# Esquema_Dispositivo.net
KiCad netlist of a schematic drawn in Altium Designer
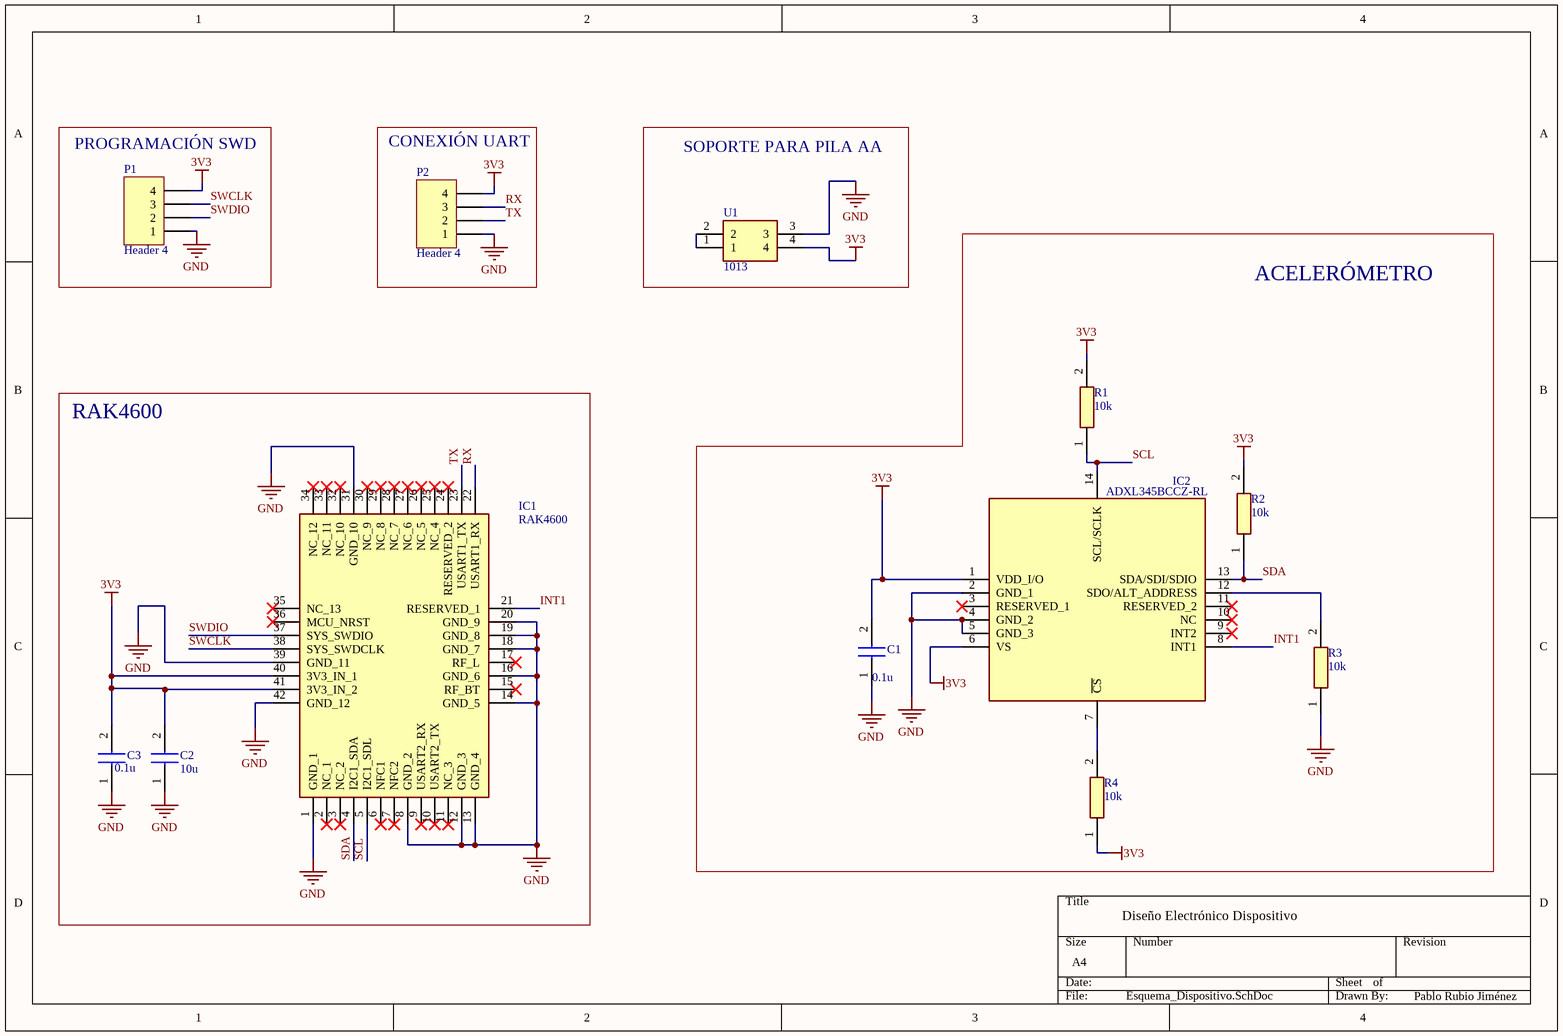
[diagram p0: Esquema_Dispositivo.SchDoc]

(export (version "E")
  (design (tool "Eeschema 10.0.6"))
  (components
    (comp (ref "C1")
      (value "0.1u")
      (footprint "SamacSys:CAPC2012X98N")
      (description "Capacitor")
      (fields
        (field (name "MANUFACTURER_PART_NUMBER") "C0805X104M5RACTU")
        (field (name "MOUSER PART NUMBER") "80-C0805X104M5RACTU")
      )
      (libsource (lib "*") (part "C0805X104M5RACTU"))
    )
    (comp (ref "C2")
      (value "10u")
      (footprint "SamacSys:CAPC1608X90N")
      (description "Capacitor")
      (fields
        (field (name "MANUFACTURER_PART_NUMBER") "0603ZD106KAT2A")
        (field (name "MOUSER PART NUMBER") "581-0603ZD106KAT2A")
      )
      (libsource (lib "*") (part "0603ZD106KAT2A"))
    )
    (comp (ref "C3")
      (value "0.1u")
      (footprint "SamacSys:CAPC2012X98N")
      (description "Capacitor")
      (fields
        (field (name "MANUFACTURER_PART_NUMBER") "C0805X104M5RACTU")
        (field (name "MOUSER PART NUMBER") "80-C0805X104M5RACTU")
      )
      (libsource (lib "*") (part "C0805X104M5RACTU"))
    )
    (comp (ref "IC1")
      (value "RAK4600")
      (footprint "SamacSys:RAK4600")
      (description "Integrated Circuit")
      (libsource (lib "SamacSys") (part "RAK4600"))
    )
    (comp (ref "IC2")
      (value "ADXL345BCCZ-RL")
      (footprint "SamacSys:ADXL345BCCZRL")
      (description "Integrated Circuit")
      (fields (field (name "MOUSER PART NUMBER") "584-ADXL345BCCZ-R"))
      (libsource (lib "*") (part "ADXL345BCCZ-RL"))
    )
    (comp (ref "P1")
      (value "Header 4")
      (footprint "HDR1X4")
      (description "Header, 4-Pin")
      (fields (field (name "PUBLISHER") "Altium Limited"))
      (libsource (lib "Miscellaneous Connectors") (part "Header 4"))
    )
    (comp (ref "P2")
      (value "Header 4")
      (footprint "HDR1X4")
      (description "Header, 4-Pin")
      (fields (field (name "PUBLISHER") "Altium Limited"))
      (libsource (lib "Miscellaneous Connectors") (part "Header 4"))
    )
    (comp (ref "R1")
      (value "10k")
      (footprint "SamacSys:RESC1005X35N")
      (description "Resistor")
      (fields
        (field (name "MANUFACTURER_PART_NUMBER") "CPF0402B10KE")
        (field (name "MOUSER PART NUMBER") "279-CPF0402B10KE")
      )
      (libsource (lib "*") (part "CPF0402B10KE"))
    )
    (comp (ref "R2")
      (value "10k")
      (footprint "SamacSys:RESC1005X35N")
      (description "Resistor")
      (fields
        (field (name "MANUFACTURER_PART_NUMBER") "CPF0402B10KE")
        (field (name "MOUSER PART NUMBER") "279-CPF0402B10KE")
      )
      (libsource (lib "*") (part "CPF0402B10KE"))
    )
    (comp (ref "R3")
      (value "10k")
      (footprint "SamacSys:RESC1005X35N")
      (description "Resistor")
      (fields
        (field (name "MANUFACTURER_PART_NUMBER") "CPF0402B10KE")
        (field (name "MOUSER PART NUMBER") "279-CPF0402B10KE")
      )
      (libsource (lib "*") (part "CPF0402B10KE"))
    )
    (comp (ref "R4")
      (value "10k")
      (footprint "SamacSys:RESC1005X35N")
      (description "Resistor")
      (fields
        (field (name "MANUFACTURER_PART_NUMBER") "CPF0402B10KE")
        (field (name "MOUSER PART NUMBER") "279-CPF0402B10KE")
      )
      (libsource (lib "*") (part "CPF0402B10KE"))
    )
    (comp (ref "U1")
      (value "1013")
      (footprint "SamacSys:1013")
      (description "Undefined or Miscellaneous")
      (fields (field (name "MOUSER PART NUMBER") "534-1013"))
      (libsource (lib "*") (part "1013"))
    )
  )
  (nets
    (net (code "1") (name "/INT1") (class "Default")
      (node (ref "IC1") (pin "21") (pinfunction "RESERVED_1_21") (pintype "passive"))
      (node (ref "IC2") (pin "8") (pinfunction "INT1_8") (pintype "passive"))
    )
    (net (code "2") (name "/RX") (class "Default")
      (node (ref "IC1") (pin "22") (pinfunction "USART1_RX_22") (pintype "passive"))
      (node (ref "P2") (pin "3") (pinfunction "3_3") (pintype "passive"))
    )
    (net (code "3") (name "/SCL") (class "Default")
      (node (ref "IC1") (pin "5") (pinfunction "I2C1_SDL_5") (pintype "passive"))
      (node (ref "IC2") (pin "14") (pinfunction "SCL/SCLK_14") (pintype "passive"))
      (node (ref "R1") (pin "1") (pinfunction "1_1") (pintype "passive"))
    )
    (net (code "4") (name "/SDA") (class "Default")
      (node (ref "IC1") (pin "4") (pinfunction "I2C1_SDA_4") (pintype "passive"))
      (node (ref "IC2") (pin "13") (pinfunction "SDA/SDI/SDIO_13") (pintype "passive"))
      (node (ref "R2") (pin "1") (pinfunction "1_1") (pintype "passive"))
    )
    (net (code "5") (name "/SWCLK") (class "Default")
      (node (ref "IC1") (pin "38") (pinfunction "SYS_SWDCLK_38") (pintype "passive"))
      (node (ref "P1") (pin "3") (pinfunction "3_3") (pintype "passive"))
    )
    (net (code "6") (name "/SWDIO") (class "Default")
      (node (ref "IC1") (pin "37") (pinfunction "SYS_SWDIO_37") (pintype "passive"))
      (node (ref "P1") (pin "2") (pinfunction "2_2") (pintype "passive"))
    )
    (net (code "7") (name "/TX") (class "Default")
      (node (ref "IC1") (pin "23") (pinfunction "USART1_TX_23") (pintype "passive"))
      (node (ref "P2") (pin "2") (pinfunction "2_2") (pintype "passive"))
    )
    (net (code "8") (name "3V3") (class "Default")
      (node (ref "C1") (pin "2") (pinfunction "2_2") (pintype "passive"))
      (node (ref "C2") (pin "2") (pinfunction "2_2") (pintype "passive"))
      (node (ref "C3") (pin "2") (pinfunction "2_2") (pintype "passive"))
      (node (ref "IC1") (pin "40") (pinfunction "3V3_IN_1_40") (pintype "passive"))
      (node (ref "IC1") (pin "41") (pinfunction "3V3_IN_2_41") (pintype "passive"))
      (node (ref "IC2") (pin "1") (pinfunction "VDD_I/O_1") (pintype "passive"))
      (node (ref "IC2") (pin "6") (pinfunction "VS_6") (pintype "passive"))
      (node (ref "P1") (pin "4") (pinfunction "4_4") (pintype "passive"))
      (node (ref "P2") (pin "4") (pinfunction "4_4") (pintype "passive"))
      (node (ref "R1") (pin "2") (pinfunction "2_2") (pintype "passive"))
      (node (ref "R2") (pin "2") (pinfunction "2_2") (pintype "passive"))
      (node (ref "R4") (pin "1") (pinfunction "1_1") (pintype "passive"))
      (node (ref "U1") (pin "4") (pinfunction "4_4") (pintype "passive"))
    )
    (net (code "9") (name "GND") (class "Default")
      (node (ref "C1") (pin "1") (pinfunction "1_1") (pintype "passive"))
      (node (ref "C2") (pin "1") (pinfunction "1_1") (pintype "passive"))
      (node (ref "C3") (pin "1") (pinfunction "1_1") (pintype "passive"))
      (node (ref "IC1") (pin "1") (pinfunction "GND_1_1") (pintype "passive"))
      (node (ref "IC1") (pin "12") (pinfunction "GND_3_12") (pintype "passive"))
      (node (ref "IC1") (pin "13") (pinfunction "GND_4_13") (pintype "passive"))
      (node (ref "IC1") (pin "14") (pinfunction "GND_5_14") (pintype "passive"))
      (node (ref "IC1") (pin "16") (pinfunction "GND_6_16") (pintype "passive"))
      (node (ref "IC1") (pin "18") (pinfunction "GND_7_18") (pintype "passive"))
      (node (ref "IC1") (pin "19") (pinfunction "GND_8_19") (pintype "passive"))
      (node (ref "IC1") (pin "20") (pinfunction "GND_9_20") (pintype "passive"))
      (node (ref "IC1") (pin "31") (pinfunction "GND_10_31") (pintype "passive"))
      (node (ref "IC1") (pin "39") (pinfunction "GND_11_39") (pintype "passive"))
      (node (ref "IC1") (pin "42") (pinfunction "GND_12_42") (pintype "passive"))
      (node (ref "IC1") (pin "8") (pinfunction "GND_2_8") (pintype "passive"))
      (node (ref "IC2") (pin "2") (pinfunction "GND_1_2") (pintype "passive"))
      (node (ref "IC2") (pin "4") (pinfunction "GND_2_4") (pintype "passive"))
      (node (ref "IC2") (pin "5") (pinfunction "GND_3_5") (pintype "passive"))
      (node (ref "P1") (pin "1") (pinfunction "1_1") (pintype "passive"))
      (node (ref "P2") (pin "1") (pinfunction "1_1") (pintype "passive"))
      (node (ref "R3") (pin "1") (pinfunction "1_1") (pintype "passive"))
      (node (ref "U1") (pin "3") (pinfunction "3_3") (pintype "passive"))
    )
    (net (code "10") (name "Net-(IC2-SDO{slash}ALT_ADDRESS)") (class "Default")
      (node (ref "IC2") (pin "12") (pinfunction "SDO/ALT_ADDRESS_12") (pintype "passive"))
      (node (ref "R3") (pin "2") (pinfunction "2_2") (pintype "passive"))
    )
    (net (code "11") (name "Net-(IC2-~{CS})") (class "Default")
      (node (ref "IC2") (pin "7") (pinfunction "~{CS}_7") (pintype "passive"))
      (node (ref "R4") (pin "2") (pinfunction "2_2") (pintype "passive"))
    )
    (net (code "12") (name "Net-(U1-Pad1)") (class "Default")
      (node (ref "U1") (pin "1") (pinfunction "1_1") (pintype "passive"))
      (node (ref "U1") (pin "2") (pinfunction "2_2") (pintype "passive"))
    )
    (net (code "13") (name "unconnected-(IC1-MCU_NRST-Pad36)") (class "Default")
      (node (ref "IC1") (pin "36") (pinfunction "MCU_NRST_36") (pintype "passive+no_connect"))
    )
    (net (code "14") (name "unconnected-(IC1-NC_1-Pad2)") (class "Default")
      (node (ref "IC1") (pin "2") (pinfunction "NC_1_2") (pintype "passive+no_connect"))
    )
    (net (code "15") (name "unconnected-(IC1-NC_2-Pad3)") (class "Default")
      (node (ref "IC1") (pin "3") (pinfunction "NC_2_3") (pintype "passive+no_connect"))
    )
    (net (code "16") (name "unconnected-(IC1-NC_3-Pad11)") (class "Default")
      (node (ref "IC1") (pin "11") (pinfunction "NC_3_11") (pintype "passive+no_connect"))
    )
    (net (code "17") (name "unconnected-(IC1-NC_4-Pad25)") (class "Default")
      (node (ref "IC1") (pin "25") (pinfunction "NC_4_25") (pintype "passive+no_connect"))
    )
    (net (code "18") (name "unconnected-(IC1-NC_5-Pad26)") (class "Default")
      (node (ref "IC1") (pin "26") (pinfunction "NC_5_26") (pintype "passive+no_connect"))
    )
    (net (code "19") (name "unconnected-(IC1-NC_6-Pad27)") (class "Default")
      (node (ref "IC1") (pin "27") (pinfunction "NC_6_27") (pintype "passive+no_connect"))
    )
    (net (code "20") (name "unconnected-(IC1-NC_7-Pad28)") (class "Default")
      (node (ref "IC1") (pin "28") (pinfunction "NC_7_28") (pintype "passive+no_connect"))
    )
    (net (code "21") (name "unconnected-(IC1-NC_8-Pad29)") (class "Default")
      (node (ref "IC1") (pin "29") (pinfunction "NC_8_29") (pintype "passive+no_connect"))
    )
    (net (code "22") (name "unconnected-(IC1-NC_9-Pad30)") (class "Default")
      (node (ref "IC1") (pin "30") (pinfunction "NC_9_30") (pintype "passive+no_connect"))
    )
    (net (code "23") (name "unconnected-(IC1-NC_10-Pad32)") (class "Default")
      (node (ref "IC1") (pin "32") (pinfunction "NC_10_32") (pintype "passive+no_connect"))
    )
    (net (code "24") (name "unconnected-(IC1-NC_11-Pad33)") (class "Default")
      (node (ref "IC1") (pin "33") (pinfunction "NC_11_33") (pintype "passive+no_connect"))
    )
    (net (code "25") (name "unconnected-(IC1-NC_12-Pad34)") (class "Default")
      (node (ref "IC1") (pin "34") (pinfunction "NC_12_34") (pintype "passive+no_connect"))
    )
    (net (code "26") (name "unconnected-(IC1-NC_13-Pad35)") (class "Default")
      (node (ref "IC1") (pin "35") (pinfunction "NC_13_35") (pintype "passive+no_connect"))
    )
    (net (code "27") (name "unconnected-(IC1-NFC1-Pad6)") (class "Default")
      (node (ref "IC1") (pin "6") (pinfunction "NFC1_6") (pintype "passive+no_connect"))
    )
    (net (code "28") (name "unconnected-(IC1-NFC2-Pad7)") (class "Default")
      (node (ref "IC1") (pin "7") (pinfunction "NFC2_7") (pintype "passive+no_connect"))
    )
    (net (code "29") (name "unconnected-(IC1-RESERVED_2-Pad24)") (class "Default")
      (node (ref "IC1") (pin "24") (pinfunction "RESERVED_2_24") (pintype "passive+no_connect"))
    )
    (net (code "30") (name "unconnected-(IC1-RF_BT-Pad15)") (class "Default")
      (node (ref "IC1") (pin "15") (pinfunction "RF_BT_15") (pintype "passive+no_connect"))
    )
    (net (code "31") (name "unconnected-(IC1-RF_L-Pad17)") (class "Default")
      (node (ref "IC1") (pin "17") (pinfunction "RF_L_17") (pintype "passive+no_connect"))
    )
    (net (code "32") (name "unconnected-(IC1-USART2_RX-Pad9)") (class "Default")
      (node (ref "IC1") (pin "9") (pinfunction "USART2_RX_9") (pintype "passive+no_connect"))
    )
    (net (code "33") (name "unconnected-(IC1-USART2_TX-Pad10)") (class "Default")
      (node (ref "IC1") (pin "10") (pinfunction "USART2_TX_10") (pintype "passive+no_connect"))
    )
    (net (code "34") (name "unconnected-(IC2-INT2-Pad9)") (class "Default")
      (node (ref "IC2") (pin "9") (pinfunction "INT2_9") (pintype "passive+no_connect"))
    )
    (net (code "35") (name "unconnected-(IC2-NC-Pad10)") (class "Default")
      (node (ref "IC2") (pin "10") (pinfunction "NC_10") (pintype "passive+no_connect"))
    )
    (net (code "36") (name "unconnected-(IC2-RESERVED_1-Pad3)") (class "Default")
      (node (ref "IC2") (pin "3") (pinfunction "RESERVED_1_3") (pintype "passive+no_connect"))
    )
    (net (code "37") (name "unconnected-(IC2-RESERVED_2-Pad11)") (class "Default")
      (node (ref "IC2") (pin "11") (pinfunction "RESERVED_2_11") (pintype "passive+no_connect"))
    )
  )
)
